# Adafruit_MPR121_Breakout.net
KiCad netlist of a schematic drawn in EAGLE
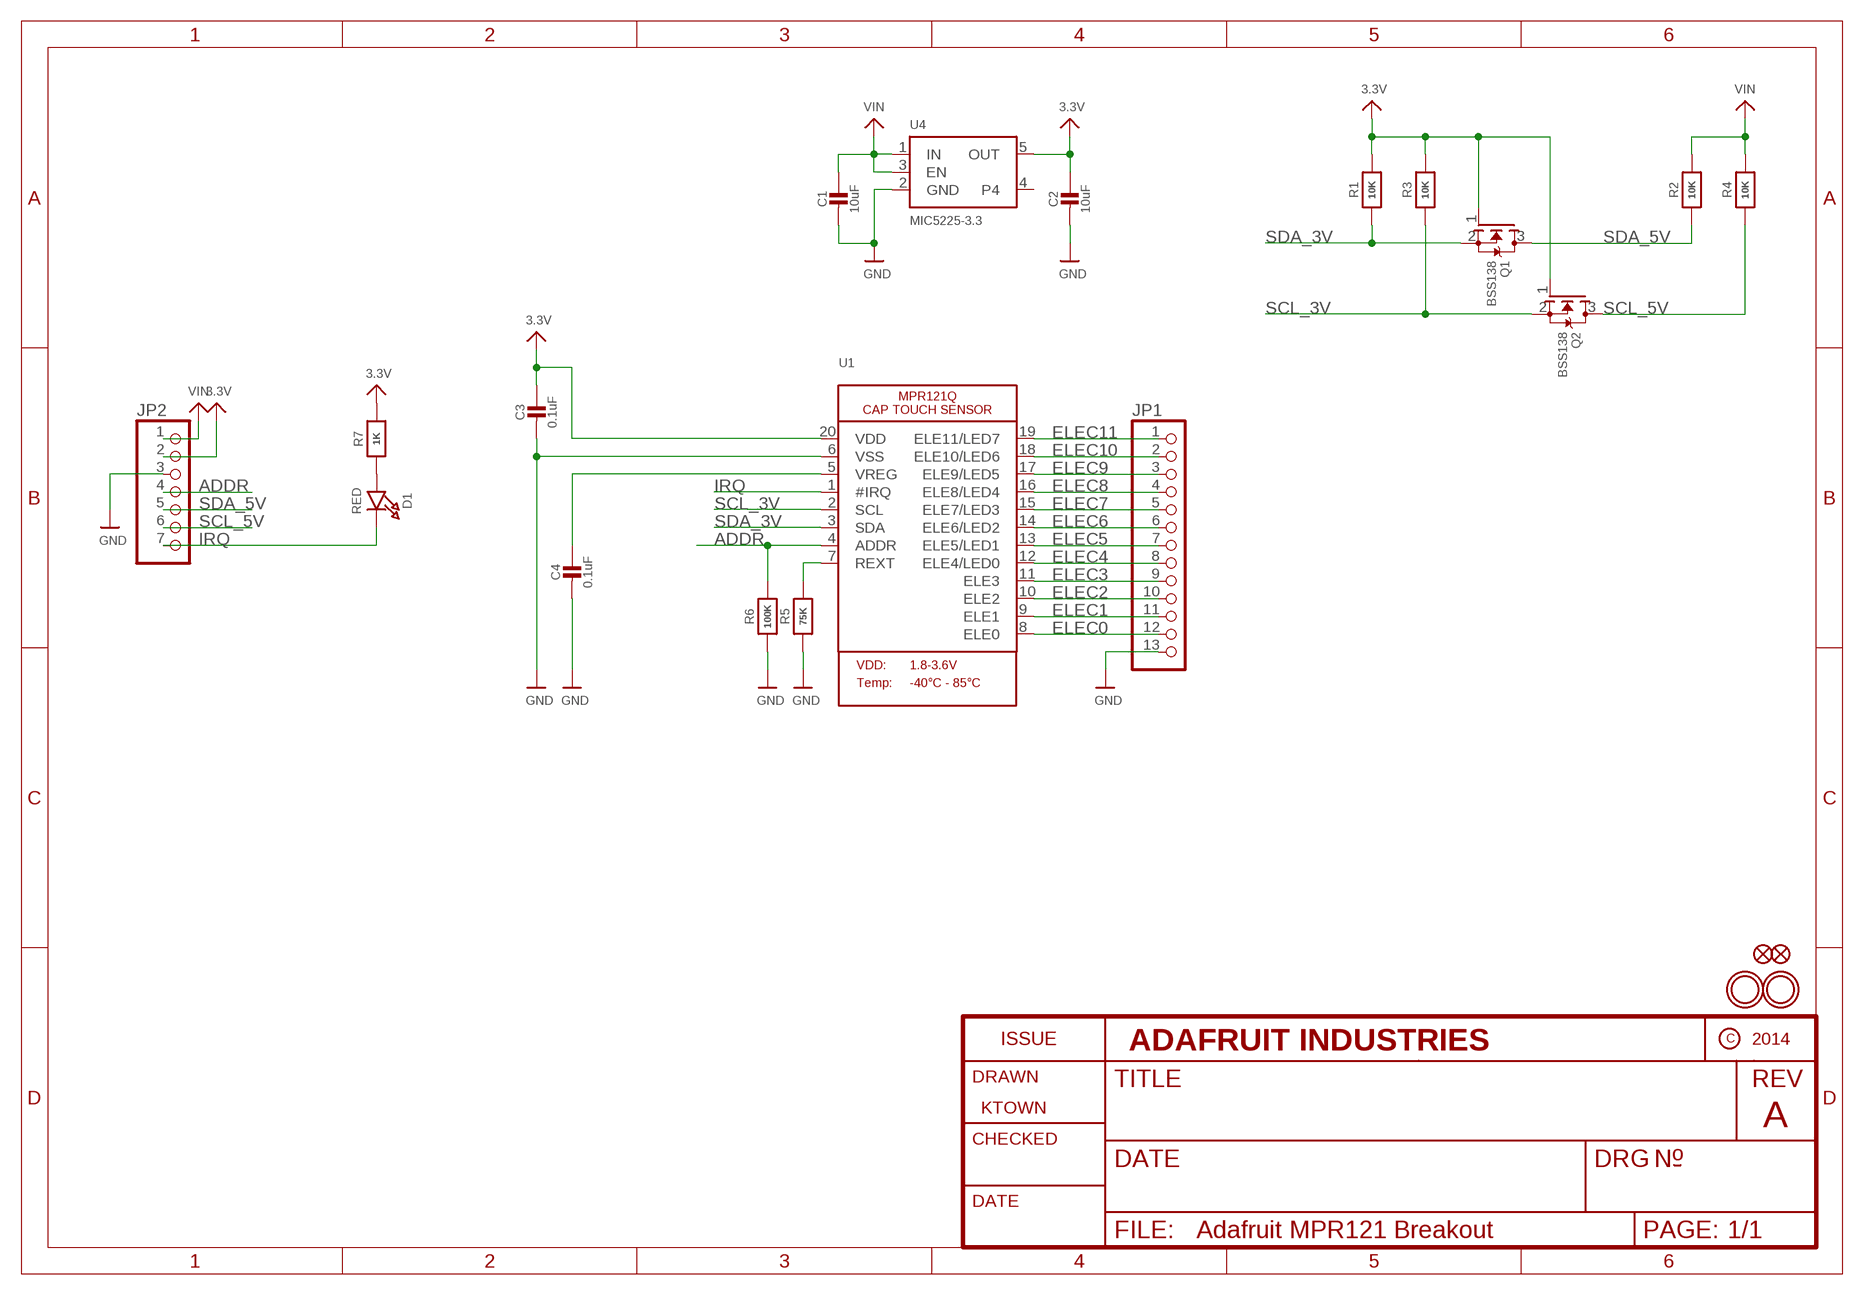
[diagram p0: schematic, sheet 1]

(export (version "E")
  (design (tool "Eeschema 10.0.6"))
  (components
    (comp (ref "C1")
      (value "10uF")
      (footprint "eagle-import:0805-NO")
      (libsource (lib "eagle-import") (part "CAP_CERAMIC0805-NOOUTLINE"))
    )
    (comp (ref "C2")
      (value "10uF")
      (footprint "eagle-import:0805-NO")
      (libsource (lib "eagle-import") (part "CAP_CERAMIC0805-NOOUTLINE"))
    )
    (comp (ref "C3")
      (value "0.1uF")
      (footprint "eagle-import:0805_10MGAP")
      (libsource (lib "eagle-import") (part "CAP_CERAMIC0805_10MGAP"))
    )
    (comp (ref "C4")
      (value "0.1uF")
      (footprint "eagle-import:0805-NO")
      (libsource (lib "eagle-import") (part "CAP_CERAMIC0805-NOOUTLINE"))
    )
    (comp (ref "D1")
      (value "RED")
      (footprint "eagle-import:CHIPLED_0805_NOOUTLINE")
      (libsource (lib "eagle-import") (part "LED0805_NOOUTLINE"))
    )
    (comp (ref "FID1")
      (value "FIDUCIAL\"\"")
      (footprint "eagle-import:FIDUCIAL_1MM")
      (libsource (lib "eagle-import") (part "FIDUCIAL{dblquote}{dblquote}"))
    )
    (comp (ref "FID2")
      (value "FIDUCIAL\"\"")
      (footprint "eagle-import:FIDUCIAL_1MM")
      (libsource (lib "eagle-import") (part "FIDUCIAL{dblquote}{dblquote}"))
    )
    (comp (ref "JP1")
      (value "HEADER-1X13")
      (footprint "eagle-import:1X13_ROUND_70")
      (libsource (lib "eagle-import") (part "HEADER-1X13"))
    )
    (comp (ref "JP2")
      (value "HEADER-1X770MIL")
      (footprint "eagle-import:1X07_ROUND_70")
      (libsource (lib "eagle-import") (part "HEADER-1X770MIL"))
    )
    (comp (ref "Q1")
      (value "BSS138")
      (footprint "eagle-import:SOT23-WIDE")
      (libsource (lib "eagle-import") (part "MOSFET-NWIDE"))
    )
    (comp (ref "Q2")
      (value "BSS138")
      (footprint "eagle-import:SOT23-WIDE")
      (libsource (lib "eagle-import") (part "MOSFET-NWIDE"))
    )
    (comp (ref "R1")
      (value "10K")
      (footprint "eagle-import:0805-NO")
      (libsource (lib "eagle-import") (part "RESISTOR0805_NOOUTLINE"))
    )
    (comp (ref "R2")
      (value "10K")
      (footprint "eagle-import:0805-NO")
      (libsource (lib "eagle-import") (part "RESISTOR0805_NOOUTLINE"))
    )
    (comp (ref "R3")
      (value "10K")
      (footprint "eagle-import:0805-NO")
      (libsource (lib "eagle-import") (part "RESISTOR0805_NOOUTLINE"))
    )
    (comp (ref "R4")
      (value "10K")
      (footprint "eagle-import:0805-NO")
      (libsource (lib "eagle-import") (part "RESISTOR0805_NOOUTLINE"))
    )
    (comp (ref "R5")
      (value "75K")
      (footprint "eagle-import:0805-NO")
      (libsource (lib "eagle-import") (part "RESISTOR0805_NOOUTLINE"))
    )
    (comp (ref "R6")
      (value "100K")
      (footprint "eagle-import:0805-NO")
      (libsource (lib "eagle-import") (part "RESISTOR0805_NOOUTLINE"))
    )
    (comp (ref "R7")
      (value "1K")
      (footprint "eagle-import:0805-NO")
      (libsource (lib "eagle-import") (part "RESISTOR0805_NOOUTLINE"))
    )
    (comp (ref "U$10")
      (value "MOUNTINGHOLE2.5")
      (footprint "eagle-import:MOUNTINGHOLE_2.5_PLATED")
      (libsource (lib "eagle-import") (part "MOUNTINGHOLE2.5"))
    )
    (comp (ref "U$11")
      (value "MOUNTINGHOLE2.5")
      (footprint "eagle-import:MOUNTINGHOLE_2.5_PLATED")
      (libsource (lib "eagle-import") (part "MOUNTINGHOLE2.5"))
    )
    (comp (ref "U1")
      (value "MPR121Q")
      (footprint "eagle-import:QFN20_3MM_NOTHERMAL")
      (libsource (lib "eagle-import") (part "MPR121Q"))
    )
    (comp (ref "U4")
      (value "MIC5225-3.3")
      (footprint "eagle-import:SOT23-5")
      (libsource (lib "eagle-import") (part "VREG_SOT23-5"))
    )
  )
  (nets
    (net (code "1") (name "/ADDR") (class "Default")
      (node (ref "JP2") (pin "4") (pinfunction "4_4") (pintype "passive"))
      (node (ref "R6") (pin "2") (pinfunction "2_2") (pintype "passive"))
      (node (ref "U1") (pin "4") (pinfunction "ADDR_4") (pintype "bidirectional"))
    )
    (net (code "2") (name "/ELEC0") (class "Default")
      (node (ref "JP1") (pin "12") (pinfunction "12_12") (pintype "passive"))
      (node (ref "U1") (pin "8") (pinfunction "ELE0_8") (pintype "bidirectional"))
    )
    (net (code "3") (name "/ELEC1") (class "Default")
      (node (ref "JP1") (pin "11") (pinfunction "11_11") (pintype "passive"))
      (node (ref "U1") (pin "9") (pinfunction "ELE1_9") (pintype "bidirectional"))
    )
    (net (code "4") (name "/ELEC2") (class "Default")
      (node (ref "JP1") (pin "10") (pinfunction "10_10") (pintype "passive"))
      (node (ref "U1") (pin "10") (pinfunction "ELE2_10") (pintype "bidirectional"))
    )
    (net (code "5") (name "/ELEC3") (class "Default")
      (node (ref "JP1") (pin "9") (pinfunction "9_9") (pintype "passive"))
      (node (ref "U1") (pin "11") (pinfunction "ELE3_11") (pintype "bidirectional"))
    )
    (net (code "6") (name "/ELEC4") (class "Default")
      (node (ref "JP1") (pin "8") (pinfunction "8_8") (pintype "passive"))
      (node (ref "U1") (pin "12") (pinfunction "ELE4/LED0_12") (pintype "bidirectional"))
    )
    (net (code "7") (name "/ELEC5") (class "Default")
      (node (ref "JP1") (pin "7") (pinfunction "7_7") (pintype "passive"))
      (node (ref "U1") (pin "13") (pinfunction "ELE5/LED1_13") (pintype "bidirectional"))
    )
    (net (code "8") (name "/ELEC6") (class "Default")
      (node (ref "JP1") (pin "6") (pinfunction "6_6") (pintype "passive"))
      (node (ref "U1") (pin "14") (pinfunction "ELE6/LED2_14") (pintype "bidirectional"))
    )
    (net (code "9") (name "/ELEC7") (class "Default")
      (node (ref "JP1") (pin "5") (pinfunction "5_5") (pintype "passive"))
      (node (ref "U1") (pin "15") (pinfunction "ELE7/LED3_15") (pintype "bidirectional"))
    )
    (net (code "10") (name "/ELEC8") (class "Default")
      (node (ref "JP1") (pin "4") (pinfunction "4_4") (pintype "passive"))
      (node (ref "U1") (pin "16") (pinfunction "ELE8/LED4_16") (pintype "bidirectional"))
    )
    (net (code "11") (name "/ELEC9") (class "Default")
      (node (ref "JP1") (pin "3") (pinfunction "3_3") (pintype "passive"))
      (node (ref "U1") (pin "17") (pinfunction "ELE9/LED5_17") (pintype "bidirectional"))
    )
    (net (code "12") (name "/ELEC10") (class "Default")
      (node (ref "JP1") (pin "2") (pinfunction "2_2") (pintype "passive"))
      (node (ref "U1") (pin "18") (pinfunction "ELE10/LED6_18") (pintype "bidirectional"))
    )
    (net (code "13") (name "/ELEC11") (class "Default")
      (node (ref "JP1") (pin "1") (pinfunction "1_1") (pintype "passive"))
      (node (ref "U1") (pin "19") (pinfunction "ELE11/LED7_19") (pintype "bidirectional"))
    )
    (net (code "14") (name "/IRQ") (class "Default")
      (node (ref "D1") (pin "C") (pinfunction "C_C") (pintype "passive"))
      (node (ref "JP2") (pin "7") (pinfunction "7_7") (pintype "passive"))
      (node (ref "U1") (pin "1") (pinfunction "#IRQ_1") (pintype "bidirectional"))
    )
    (net (code "15") (name "/SCL_3V") (class "Default")
      (node (ref "Q2") (pin "2") (pinfunction "S_2") (pintype "bidirectional"))
      (node (ref "R3") (pin "1") (pinfunction "1_1") (pintype "passive"))
      (node (ref "U1") (pin "2") (pinfunction "SCL_2") (pintype "bidirectional"))
    )
    (net (code "16") (name "/SCL_5V") (class "Default")
      (node (ref "JP2") (pin "6") (pinfunction "6_6") (pintype "passive"))
      (node (ref "Q2") (pin "3") (pinfunction "D_3") (pintype "bidirectional"))
      (node (ref "R4") (pin "1") (pinfunction "1_1") (pintype "passive"))
    )
    (net (code "17") (name "/SDA_3V") (class "Default")
      (node (ref "Q1") (pin "2") (pinfunction "S_2") (pintype "bidirectional"))
      (node (ref "R1") (pin "1") (pinfunction "1_1") (pintype "passive"))
      (node (ref "U1") (pin "3") (pinfunction "SDA_3") (pintype "bidirectional"))
    )
    (net (code "18") (name "/SDA_5V") (class "Default")
      (node (ref "JP2") (pin "5") (pinfunction "5_5") (pintype "passive"))
      (node (ref "Q1") (pin "3") (pinfunction "D_3") (pintype "bidirectional"))
      (node (ref "R2") (pin "1") (pinfunction "1_1") (pintype "passive"))
    )
    (net (code "19") (name "3.3V") (class "Default")
      (node (ref "C2") (pin "1") (pinfunction "1_1") (pintype "passive"))
      (node (ref "C3") (pin "1") (pinfunction "1_1") (pintype "passive"))
      (node (ref "JP2") (pin "2") (pinfunction "2_2") (pintype "passive"))
      (node (ref "Q1") (pin "1") (pinfunction "G_1") (pintype "bidirectional"))
      (node (ref "Q2") (pin "1") (pinfunction "G_1") (pintype "bidirectional"))
      (node (ref "R1") (pin "2") (pinfunction "2_2") (pintype "passive"))
      (node (ref "R3") (pin "2") (pinfunction "2_2") (pintype "passive"))
      (node (ref "R7") (pin "2") (pinfunction "2_2") (pintype "passive"))
      (node (ref "U1") (pin "20") (pinfunction "VDD_20") (pintype "power_in"))
      (node (ref "U4") (pin "5") (pinfunction "OUT_5") (pintype "power_in"))
    )
    (net (code "20") (name "GND") (class "Default")
      (node (ref "C1") (pin "2") (pinfunction "2_2") (pintype "passive"))
      (node (ref "C2") (pin "2") (pinfunction "2_2") (pintype "passive"))
      (node (ref "C3") (pin "2") (pinfunction "2_2") (pintype "passive"))
      (node (ref "C4") (pin "2") (pinfunction "2_2") (pintype "passive"))
      (node (ref "JP1") (pin "13") (pinfunction "13_13") (pintype "passive"))
      (node (ref "JP2") (pin "3") (pinfunction "3_3") (pintype "passive"))
      (node (ref "R5") (pin "1") (pinfunction "1_1") (pintype "passive"))
      (node (ref "R6") (pin "1") (pinfunction "1_1") (pintype "passive"))
      (node (ref "U1") (pin "6") (pinfunction "VSS_6") (pintype "power_in"))
      (node (ref "U4") (pin "2") (pinfunction "GND_2") (pintype "power_in"))
    )
    (net (code "21") (name "Net-(D1-PadA)") (class "Default")
      (node (ref "D1") (pin "A") (pinfunction "A_A") (pintype "passive"))
      (node (ref "R7") (pin "1") (pinfunction "1_1") (pintype "passive"))
    )
    (net (code "22") (name "Net-(U1-REXT)") (class "Default")
      (node (ref "R5") (pin "2") (pinfunction "2_2") (pintype "passive"))
      (node (ref "U1") (pin "7") (pinfunction "REXT_7") (pintype "bidirectional"))
    )
    (net (code "23") (name "Net-(U1-VREG)") (class "Default")
      (node (ref "C4") (pin "1") (pinfunction "1_1") (pintype "passive"))
      (node (ref "U1") (pin "5") (pinfunction "VREG_5") (pintype "bidirectional"))
    )
    (net (code "24") (name "VIN") (class "Default")
      (node (ref "C1") (pin "1") (pinfunction "1_1") (pintype "passive"))
      (node (ref "JP2") (pin "1") (pinfunction "1_1") (pintype "passive"))
      (node (ref "R2") (pin "2") (pinfunction "2_2") (pintype "passive"))
      (node (ref "R4") (pin "2") (pinfunction "2_2") (pintype "passive"))
      (node (ref "U4") (pin "1") (pinfunction "IN_1") (pintype "power_in"))
      (node (ref "U4") (pin "3") (pinfunction "EN_3") (pintype "input"))
    )
    (net (code "25") (name "unconnected-(U4-P4-Pad4)") (class "Default")
      (node (ref "U4") (pin "4") (pinfunction "P4_4") (pintype "bidirectional"))
    )
  )
)
